# czujnik_dotyku.net
KiCad netlist of a schematic drawn in Altium Designer
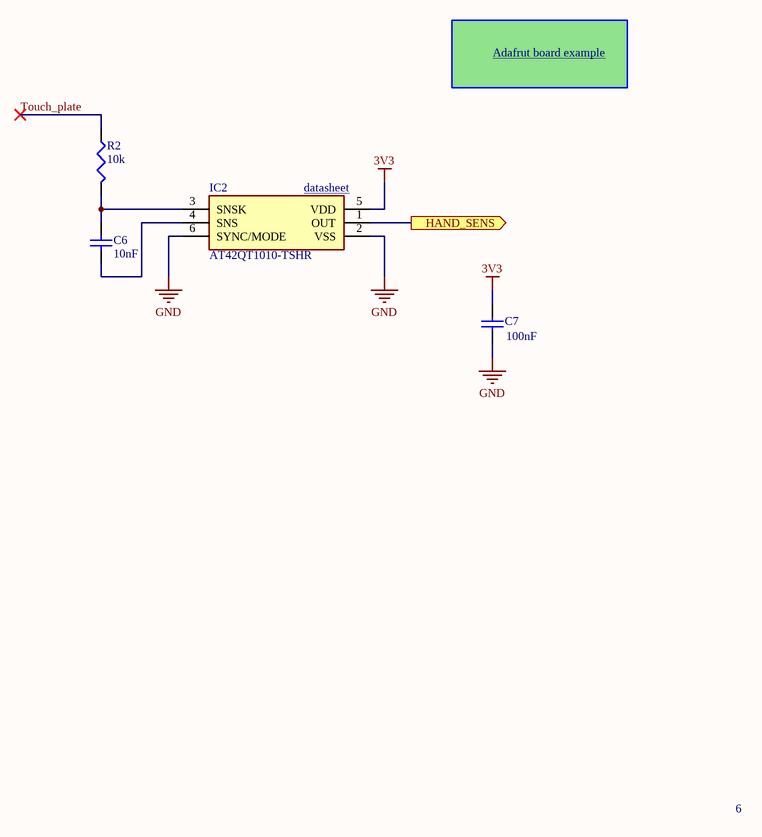
[diagram p0: czujnik_dotyku.SchDoc]

(export (version "E")
  (design (tool "Eeschema 10.0.6"))
  (components
    (comp (ref "C6")
      (value "10nF")
      (footprint "C0805")
      (description "Capacitor")
      (fields (field (name "Comment") "Cap") (field (name "PUBLISHER") "Altium Limited"))
      (libsource (lib "Miscellaneous Devices") (part "Cap"))
    )
    (comp (ref "C7")
      (value "100nF")
      (footprint "C0805")
      (description "Capacitor")
      (fields (field (name "Comment") "Cap") (field (name "PUBLISHER") "Altium Limited"))
      (libsource (lib "Miscellaneous Devices") (part "Cap"))
    )
    (comp (ref "IC2")
      (value "AT42QT1010-TSHR")
      (footprint "SOT95P280X145-6N")
      (description "capacitive touch sensor")
      (fields (field (name "MOUSER PART NUMBER") "556-AT42QT1010-TSHR"))
      (libsource (lib "lib") (part "AT42QT1010-TSHR"))
    )
    (comp (ref "R2")
      (value "10k")
      (footprint "R0603")
      (description "Resistor")
      (fields (field (name "Comment") "Res3") (field (name "PUBLISHER") "Altium Limited"))
      (libsource (lib "Miscellaneous Devices") (part "Res3"))
    )
  )
  (nets
    (net (code "1") (name "/HAND_SENS") (class "Default")
      (node (ref "IC2") (pin "1") (pinfunction "OUT_1") (pintype "passive"))
    )
    (net (code "2") (name "/Touch_plate") (class "Default")
      (node (ref "R2") (pin "2") (pinfunction "2_2") (pintype "passive+no_connect"))
    )
    (net (code "3") (name "3V3") (class "Default")
      (node (ref "C7") (pin "2") (pinfunction "2_2") (pintype "passive"))
      (node (ref "IC2") (pin "5") (pinfunction "VDD_5") (pintype "passive"))
    )
    (net (code "4") (name "GND") (class "Default")
      (node (ref "C7") (pin "1") (pinfunction "1_1") (pintype "passive"))
      (node (ref "IC2") (pin "2") (pinfunction "VSS_2") (pintype "passive"))
      (node (ref "IC2") (pin "6") (pinfunction "SYNC/MODE_6") (pintype "passive"))
    )
    (net (code "5") (name "Net-(IC2-SNS)") (class "Default")
      (node (ref "C6") (pin "1") (pinfunction "1_1") (pintype "passive"))
      (node (ref "IC2") (pin "4") (pinfunction "SNS_4") (pintype "passive"))
    )
    (net (code "6") (name "Net-(IC2-SNSK)") (class "Default")
      (node (ref "C6") (pin "2") (pinfunction "2_2") (pintype "passive"))
      (node (ref "IC2") (pin "3") (pinfunction "SNSK_3") (pintype "passive"))
      (node (ref "R2") (pin "1") (pinfunction "1_1") (pintype "passive"))
    )
  )
)
